# main.net
KiCad netlist of a schematic drawn in EAGLE
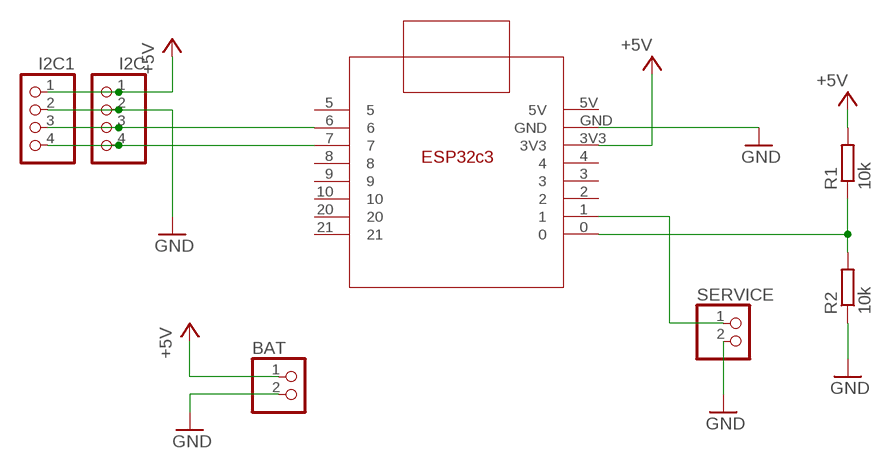
[diagram p0: schematic, sheet 1]

(export (version "E")
  (design (tool "Eeschema 10.0.6"))
  (components
    (comp (ref "BAT")
      (value "PINHD-1X2")
      (footprint "eagle-import:1X02")
      (libsource (lib "eagle-import") (part "PINHD-1X2"))
    )
    (comp (ref "I2C")
      (value "PINHD-1X4")
      (footprint "eagle-import:1X04")
      (libsource (lib "eagle-import") (part "PINHD-1X4"))
    )
    (comp (ref "I2C1")
      (value "PINHD-1X4")
      (footprint "eagle-import:1X04")
      (libsource (lib "eagle-import") (part "PINHD-1X4"))
    )
    (comp (ref "R1")
      (value "10k")
      (footprint "eagle-import:R0805")
      (libsource (lib "eagle-import") (part "R-EU_R0805"))
    )
    (comp (ref "R2")
      (value "10k")
      (footprint "eagle-import:R0805")
      (libsource (lib "eagle-import") (part "R-EU_R0805"))
    )
    (comp (ref "SERVICE")
      (value "PINHD-1X2")
      (footprint "eagle-import:1X02")
      (libsource (lib "eagle-import") (part "PINHD-1X2"))
    )
    (comp (ref "U$2")
      (value "ESP32C3SMD")
      (footprint "eagle-import:ESP32C3_SMD")
      (libsource (lib "eagle-import") (part "ESP32C3SMD"))
    )
  )
  (nets
    (net (code "1") (name "+5V") (class "Default")
      (node (ref "BAT") (pin "1") (pinfunction "1_1") (pintype "passive"))
      (node (ref "I2C") (pin "1") (pinfunction "1_1") (pintype "passive"))
      (node (ref "I2C1") (pin "1") (pinfunction "1_1") (pintype "passive"))
      (node (ref "R1") (pin "2") (pinfunction "2_2") (pintype "passive"))
      (node (ref "U$2") (pin "3V3") (pinfunction "3V3_3V3") (pintype "bidirectional"))
    )
    (net (code "2") (name "GND") (class "Default")
      (node (ref "BAT") (pin "2") (pinfunction "2_2") (pintype "passive"))
      (node (ref "I2C") (pin "2") (pinfunction "2_2") (pintype "passive"))
      (node (ref "I2C1") (pin "2") (pinfunction "2_2") (pintype "passive"))
      (node (ref "R2") (pin "1") (pinfunction "1_1") (pintype "passive"))
      (node (ref "SERVICE") (pin "2") (pinfunction "2_2") (pintype "passive"))
      (node (ref "U$2") (pin "GND") (pinfunction "GND_GND") (pintype "bidirectional"))
    )
    (net (code "3") (name "Net-(I2C-Pad3)") (class "Default")
      (node (ref "I2C") (pin "3") (pinfunction "3_3") (pintype "passive"))
      (node (ref "I2C1") (pin "3") (pinfunction "3_3") (pintype "passive"))
      (node (ref "U$2") (pin "6") (pinfunction "6_6") (pintype "bidirectional"))
    )
    (net (code "4") (name "Net-(I2C-Pad4)") (class "Default")
      (node (ref "I2C") (pin "4") (pinfunction "4_4") (pintype "passive"))
      (node (ref "I2C1") (pin "4") (pinfunction "4_4") (pintype "passive"))
      (node (ref "U$2") (pin "7") (pinfunction "7_7") (pintype "bidirectional"))
    )
    (net (code "5") (name "Net-(R1-Pad1)") (class "Default")
      (node (ref "R1") (pin "1") (pinfunction "1_1") (pintype "passive"))
      (node (ref "R2") (pin "2") (pinfunction "2_2") (pintype "passive"))
      (node (ref "U$2") (pin "0") (pinfunction "0_0") (pintype "bidirectional"))
    )
    (net (code "6") (name "Net-(SERVICE-Pad1)") (class "Default")
      (node (ref "SERVICE") (pin "1") (pinfunction "1_1") (pintype "passive"))
      (node (ref "U$2") (pin "1") (pinfunction "1_1") (pintype "bidirectional"))
    )
    (net (code "7") (name "unconnected-(U$2-Pad2)") (class "Default")
      (node (ref "U$2") (pin "2") (pinfunction "2_2") (pintype "bidirectional"))
    )
    (net (code "8") (name "unconnected-(U$2-Pad3)") (class "Default")
      (node (ref "U$2") (pin "3") (pinfunction "3_3") (pintype "bidirectional"))
    )
    (net (code "9") (name "unconnected-(U$2-Pad4)") (class "Default")
      (node (ref "U$2") (pin "4") (pinfunction "4_4") (pintype "bidirectional"))
    )
    (net (code "10") (name "unconnected-(U$2-Pad5)") (class "Default")
      (node (ref "U$2") (pin "5") (pinfunction "5_5") (pintype "bidirectional"))
    )
    (net (code "11") (name "unconnected-(U$2-Pad5V)") (class "Default")
      (node (ref "U$2") (pin "5V") (pinfunction "5V_5V") (pintype "bidirectional"))
    )
    (net (code "12") (name "unconnected-(U$2-Pad8)") (class "Default")
      (node (ref "U$2") (pin "8") (pinfunction "8_8") (pintype "bidirectional"))
    )
    (net (code "13") (name "unconnected-(U$2-Pad9)") (class "Default")
      (node (ref "U$2") (pin "9") (pinfunction "9_9") (pintype "bidirectional"))
    )
    (net (code "14") (name "unconnected-(U$2-Pad10)") (class "Default")
      (node (ref "U$2") (pin "10") (pinfunction "10_10") (pintype "bidirectional"))
    )
    (net (code "15") (name "unconnected-(U$2-Pad20)") (class "Default")
      (node (ref "U$2") (pin "20") (pinfunction "20_20") (pintype "bidirectional"))
    )
    (net (code "16") (name "unconnected-(U$2-Pad21)") (class "Default")
      (node (ref "U$2") (pin "21") (pinfunction "21_21") (pintype "bidirectional"))
    )
  )
)
